# 32u4_pocket.net
KiCad netlist of a schematic drawn in EAGLE
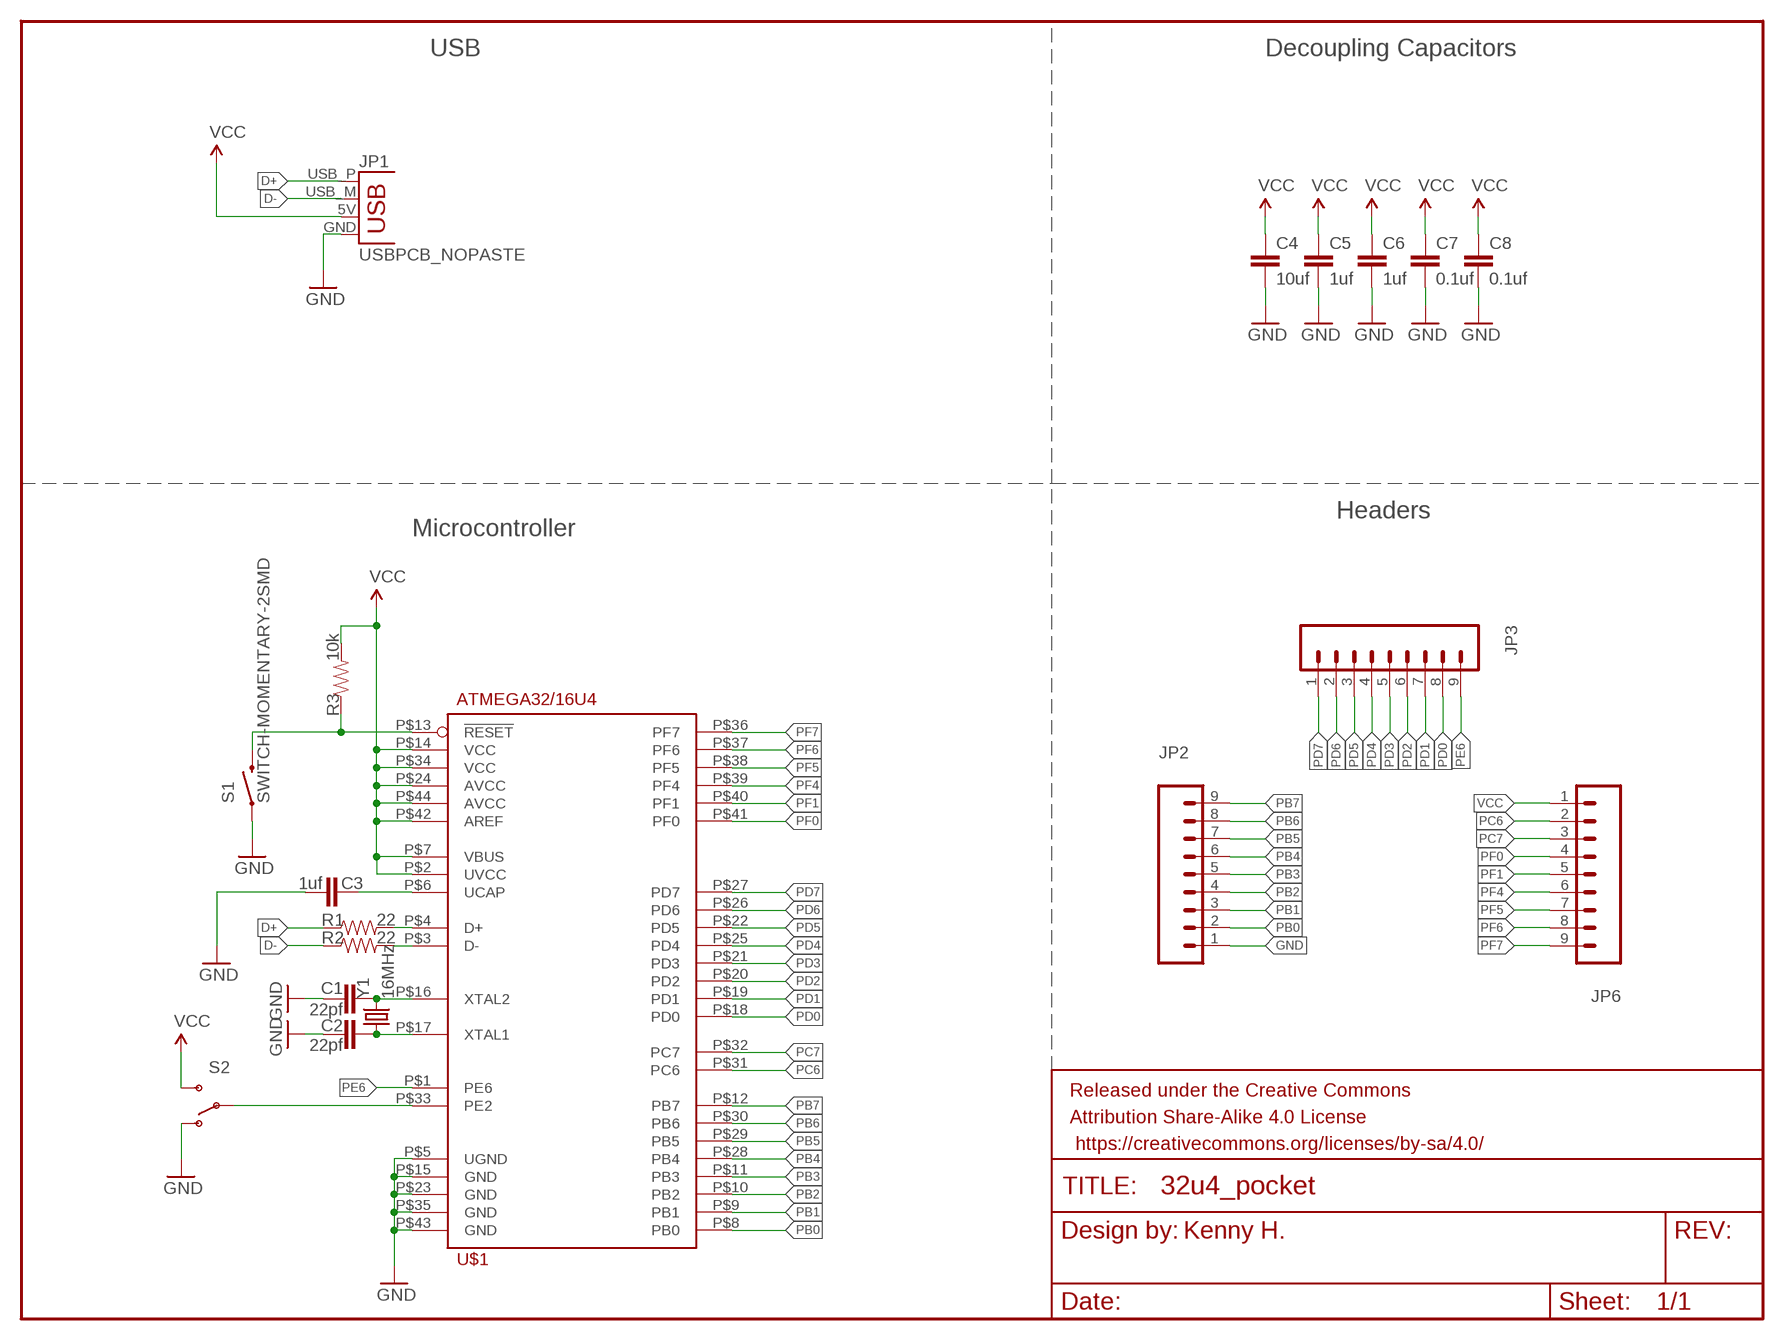
[diagram p0: schematic, sheet 1]

(export (version "E")
  (design (tool "Eeschema 10.0.6"))
  (components
    (comp (ref "C1")
      (value "22pf")
      (footprint "eagle-import:0603-CAP")
      (libsource (lib "eagle-import") (part "CAP0603-CAP"))
    )
    (comp (ref "C2")
      (value "22pf")
      (footprint "eagle-import:0603-CAP")
      (libsource (lib "eagle-import") (part "CAP0603-CAP"))
    )
    (comp (ref "C3")
      (value "1uf")
      (footprint "eagle-import:0603-CAP")
      (libsource (lib "eagle-import") (part "CAP0603-CAP"))
    )
    (comp (ref "C4")
      (value "10uf")
      (footprint "eagle-import:0603-CAP")
      (libsource (lib "eagle-import") (part "CAP0603-CAP"))
    )
    (comp (ref "C5")
      (value "1uf")
      (footprint "eagle-import:0603-CAP")
      (libsource (lib "eagle-import") (part "CAP0603-CAP"))
    )
    (comp (ref "C6")
      (value "1uf")
      (footprint "eagle-import:0603-CAP")
      (libsource (lib "eagle-import") (part "CAP0603-CAP"))
    )
    (comp (ref "C7")
      (value "0.1uf")
      (footprint "eagle-import:0603-CAP")
      (libsource (lib "eagle-import") (part "CAP0603-CAP"))
    )
    (comp (ref "C8")
      (value "0.1uf")
      (footprint "eagle-import:0603-CAP")
      (libsource (lib "eagle-import") (part "CAP0603-CAP"))
    )
    (comp (ref "FRAME1")
      (value "FRAME-LETTER")
      (footprint "eagle-import:CREATIVE_COMMONS")
      (libsource (lib "eagle-import") (part "FRAME-LETTER"))
    )
    (comp (ref "JP1")
      (value "USBPCB_NOPASTE")
      (footprint "eagle-import:USB-A-PCB-NOPASTE")
      (libsource (lib "eagle-import") (part "USBPCB_NOPASTE"))
    )
    (comp (ref "JP2")
      (value "M09LOCK-LONGPADS")
      (footprint "eagle-import:1X09_LOCK_LONGPADS")
      (libsource (lib "eagle-import") (part "M09LOCK-LONGPADS"))
    )
    (comp (ref "JP3")
      (value "M09LOCK-LONGPADS")
      (footprint "eagle-import:1X09_LOCK_LONGPADS")
      (libsource (lib "eagle-import") (part "M09LOCK-LONGPADS"))
    )
    (comp (ref "JP6")
      (value "M09LOCK-LONGPADS")
      (footprint "eagle-import:1X09_LOCK_LONGPADS")
      (libsource (lib "eagle-import") (part "M09LOCK-LONGPADS"))
    )
    (comp (ref "R1")
      (value "22")
      (footprint "eagle-import:0603-RES")
      (libsource (lib "eagle-import") (part "RESISTOR0603-RES"))
    )
    (comp (ref "R2")
      (value "22")
      (footprint "eagle-import:0603-RES")
      (libsource (lib "eagle-import") (part "RESISTOR0603-RES"))
    )
    (comp (ref "R3")
      (value "10k")
      (footprint "eagle-import:0603-RES")
      (libsource (lib "eagle-import") (part "RESISTOR0603-RES"))
    )
    (comp (ref "S1")
      (value "SWITCH-MOMENTARY-2SMD")
      (footprint "eagle-import:TACTILE-SWITCH-SMD")
      (libsource (lib "eagle-import") (part "SWITCH-MOMENTARY-2SMD"))
    )
    (comp (ref "S2")
      (value "SWITCH-SPDT-SMD-A")
      (footprint "eagle-import:SWITCH-SPST-SMD-A")
      (libsource (lib "eagle-import") (part "SWITCH-SPDT-SMD-A"))
    )
    (comp (ref "U$1")
      (value "ATMEGA32/16U4")
      (footprint "eagle-import:TQFP_44_0.8MM")
      (libsource (lib "eagle-import") (part "ATMEGA32/16U4"))
    )
    (comp (ref "Y1")
      (value "16MHz")
      (footprint "eagle-import:HC49US")
      (libsource (lib "eagle-import") (part "CRYSTALHC49US"))
    )
  )
  (nets
    (net (code "1") (name "D+") (class "Default")
      (node (ref "JP1") (pin "USB_P") (pinfunction "D+_USB_P") (pintype "bidirectional"))
      (node (ref "R1") (pin "1") (pinfunction "1_1") (pintype "passive"))
    )
    (net (code "2") (name "D-") (class "Default")
      (node (ref "JP1") (pin "USB_M") (pinfunction "D-_USB_M") (pintype "bidirectional"))
      (node (ref "R2") (pin "1") (pinfunction "1_1") (pintype "passive"))
    )
    (net (code "3") (name "GND") (class "Default")
      (node (ref "C1") (pin "1") (pinfunction "1_1") (pintype "passive"))
      (node (ref "C2") (pin "1") (pinfunction "1_1") (pintype "passive"))
      (node (ref "C3") (pin "2") (pinfunction "2_2") (pintype "passive"))
      (node (ref "C4") (pin "2") (pinfunction "2_2") (pintype "passive"))
      (node (ref "C5") (pin "2") (pinfunction "2_2") (pintype "passive"))
      (node (ref "C6") (pin "2") (pinfunction "2_2") (pintype "passive"))
      (node (ref "C7") (pin "2") (pinfunction "2_2") (pintype "passive"))
      (node (ref "C8") (pin "2") (pinfunction "2_2") (pintype "passive"))
      (node (ref "JP1") (pin "GND") (pinfunction "GND_GND") (pintype "bidirectional"))
      (node (ref "JP2") (pin "1") (pinfunction "1_1") (pintype "passive"))
      (node (ref "S1") (pin "1") (pinfunction "1_1") (pintype "passive"))
      (node (ref "S2") (pin "1") (pinfunction "O_1") (pintype "passive"))
      (node (ref "U$1") (pin "P$15") (pinfunction "GND_P$15") (pintype "power_in"))
      (node (ref "U$1") (pin "P$23") (pinfunction "GND_P$23") (pintype "power_in"))
      (node (ref "U$1") (pin "P$35") (pinfunction "GND_P$35") (pintype "power_in"))
      (node (ref "U$1") (pin "P$43") (pinfunction "GND_P$43") (pintype "power_in"))
      (node (ref "U$1") (pin "P$5") (pinfunction "UGND_P$5") (pintype "power_in"))
    )
    (net (code "4") (name "Net-(S1-2)") (class "Default")
      (node (ref "R3") (pin "1") (pinfunction "1_1") (pintype "passive"))
      (node (ref "S1") (pin "3") (pinfunction "2_3") (pintype "passive"))
      (node (ref "U$1") (pin "P$13") (pinfunction "~{RESET}_P$13") (pintype "input"))
    )
    (net (code "5") (name "Net-(S2-P)") (class "Default")
      (node (ref "S2") (pin "2") (pinfunction "P_2") (pintype "passive"))
      (node (ref "U$1") (pin "P$33") (pinfunction "PE2_P$33") (pintype "bidirectional"))
    )
    (net (code "6") (name "Net-(U$1-D+)") (class "Default")
      (node (ref "R1") (pin "2") (pinfunction "2_2") (pintype "passive"))
      (node (ref "U$1") (pin "P$4") (pinfunction "D+_P$4") (pintype "bidirectional"))
    )
    (net (code "7") (name "Net-(U$1-D-)") (class "Default")
      (node (ref "R2") (pin "2") (pinfunction "2_2") (pintype "passive"))
      (node (ref "U$1") (pin "P$3") (pinfunction "D-_P$3") (pintype "bidirectional"))
    )
    (net (code "8") (name "Net-(U$1-UCAP)") (class "Default")
      (node (ref "C3") (pin "1") (pinfunction "1_1") (pintype "passive"))
      (node (ref "U$1") (pin "P$6") (pinfunction "UCAP_P$6") (pintype "output"))
    )
    (net (code "9") (name "Net-(U$1-XTAL1)") (class "Default")
      (node (ref "C2") (pin "2") (pinfunction "2_2") (pintype "passive"))
      (node (ref "U$1") (pin "P$17") (pinfunction "XTAL1_P$17") (pintype "input"))
      (node (ref "Y1") (pin "1") (pinfunction "1_1") (pintype "passive"))
    )
    (net (code "10") (name "Net-(U$1-XTAL2)") (class "Default")
      (node (ref "C1") (pin "2") (pinfunction "2_2") (pintype "passive"))
      (node (ref "U$1") (pin "P$16") (pinfunction "XTAL2_P$16") (pintype "input"))
      (node (ref "Y1") (pin "2") (pinfunction "2_2") (pintype "passive"))
    )
    (net (code "11") (name "PB0") (class "Default")
      (node (ref "JP2") (pin "2") (pinfunction "2_2") (pintype "passive"))
      (node (ref "U$1") (pin "P$8") (pinfunction "PB0_P$8") (pintype "bidirectional"))
    )
    (net (code "12") (name "PB1") (class "Default")
      (node (ref "JP2") (pin "3") (pinfunction "3_3") (pintype "passive"))
      (node (ref "U$1") (pin "P$9") (pinfunction "PB1_P$9") (pintype "bidirectional"))
    )
    (net (code "13") (name "PB2") (class "Default")
      (node (ref "JP2") (pin "4") (pinfunction "4_4") (pintype "passive"))
      (node (ref "U$1") (pin "P$10") (pinfunction "PB2_P$10") (pintype "bidirectional"))
    )
    (net (code "14") (name "PB3") (class "Default")
      (node (ref "JP2") (pin "5") (pinfunction "5_5") (pintype "passive"))
      (node (ref "U$1") (pin "P$11") (pinfunction "PB3_P$11") (pintype "bidirectional"))
    )
    (net (code "15") (name "PB4") (class "Default")
      (node (ref "JP2") (pin "6") (pinfunction "6_6") (pintype "passive"))
      (node (ref "U$1") (pin "P$28") (pinfunction "PB4_P$28") (pintype "bidirectional"))
    )
    (net (code "16") (name "PB5") (class "Default")
      (node (ref "JP2") (pin "7") (pinfunction "7_7") (pintype "passive"))
      (node (ref "U$1") (pin "P$29") (pinfunction "PB5_P$29") (pintype "bidirectional"))
    )
    (net (code "17") (name "PB6") (class "Default")
      (node (ref "JP2") (pin "8") (pinfunction "8_8") (pintype "passive"))
      (node (ref "U$1") (pin "P$30") (pinfunction "PB6_P$30") (pintype "bidirectional"))
    )
    (net (code "18") (name "PB7") (class "Default")
      (node (ref "JP2") (pin "9") (pinfunction "9_9") (pintype "passive"))
      (node (ref "U$1") (pin "P$12") (pinfunction "PB7_P$12") (pintype "bidirectional"))
    )
    (net (code "19") (name "PC6") (class "Default")
      (node (ref "JP6") (pin "2") (pinfunction "2_2") (pintype "passive"))
      (node (ref "U$1") (pin "P$31") (pinfunction "PC6_P$31") (pintype "bidirectional"))
    )
    (net (code "20") (name "PC7") (class "Default")
      (node (ref "JP6") (pin "3") (pinfunction "3_3") (pintype "passive"))
      (node (ref "U$1") (pin "P$32") (pinfunction "PC7_P$32") (pintype "bidirectional"))
    )
    (net (code "21") (name "PD0") (class "Default")
      (node (ref "JP3") (pin "8") (pinfunction "8_8") (pintype "passive"))
      (node (ref "U$1") (pin "P$18") (pinfunction "PD0_P$18") (pintype "bidirectional"))
    )
    (net (code "22") (name "PD1") (class "Default")
      (node (ref "JP3") (pin "7") (pinfunction "7_7") (pintype "passive"))
      (node (ref "U$1") (pin "P$19") (pinfunction "PD1_P$19") (pintype "bidirectional"))
    )
    (net (code "23") (name "PD2") (class "Default")
      (node (ref "JP3") (pin "6") (pinfunction "6_6") (pintype "passive"))
      (node (ref "U$1") (pin "P$20") (pinfunction "PD2_P$20") (pintype "bidirectional"))
    )
    (net (code "24") (name "PD3") (class "Default")
      (node (ref "JP3") (pin "5") (pinfunction "5_5") (pintype "passive"))
      (node (ref "U$1") (pin "P$21") (pinfunction "PD3_P$21") (pintype "bidirectional"))
    )
    (net (code "25") (name "PD4") (class "Default")
      (node (ref "JP3") (pin "4") (pinfunction "4_4") (pintype "passive"))
      (node (ref "U$1") (pin "P$25") (pinfunction "PD4_P$25") (pintype "bidirectional"))
    )
    (net (code "26") (name "PD5") (class "Default")
      (node (ref "JP3") (pin "3") (pinfunction "3_3") (pintype "passive"))
      (node (ref "U$1") (pin "P$22") (pinfunction "PD5_P$22") (pintype "bidirectional"))
    )
    (net (code "27") (name "PD6") (class "Default")
      (node (ref "JP3") (pin "2") (pinfunction "2_2") (pintype "passive"))
      (node (ref "U$1") (pin "P$26") (pinfunction "PD6_P$26") (pintype "bidirectional"))
    )
    (net (code "28") (name "PD7") (class "Default")
      (node (ref "JP3") (pin "1") (pinfunction "1_1") (pintype "passive"))
      (node (ref "U$1") (pin "P$27") (pinfunction "PD7_P$27") (pintype "bidirectional"))
    )
    (net (code "29") (name "PE6") (class "Default")
      (node (ref "JP3") (pin "9") (pinfunction "9_9") (pintype "passive"))
      (node (ref "U$1") (pin "P$1") (pinfunction "PE6_P$1") (pintype "bidirectional"))
    )
    (net (code "30") (name "PF0") (class "Default")
      (node (ref "JP6") (pin "4") (pinfunction "4_4") (pintype "passive"))
      (node (ref "U$1") (pin "P$41") (pinfunction "PF0_P$41") (pintype "bidirectional"))
    )
    (net (code "31") (name "PF1") (class "Default")
      (node (ref "JP6") (pin "5") (pinfunction "5_5") (pintype "passive"))
      (node (ref "U$1") (pin "P$40") (pinfunction "PF1_P$40") (pintype "bidirectional"))
    )
    (net (code "32") (name "PF4") (class "Default")
      (node (ref "JP6") (pin "6") (pinfunction "6_6") (pintype "passive"))
      (node (ref "U$1") (pin "P$39") (pinfunction "PF4_P$39") (pintype "bidirectional"))
    )
    (net (code "33") (name "PF5") (class "Default")
      (node (ref "JP6") (pin "7") (pinfunction "7_7") (pintype "passive"))
      (node (ref "U$1") (pin "P$38") (pinfunction "PF5_P$38") (pintype "bidirectional"))
    )
    (net (code "34") (name "PF6") (class "Default")
      (node (ref "JP6") (pin "8") (pinfunction "8_8") (pintype "passive"))
      (node (ref "U$1") (pin "P$37") (pinfunction "PF6_P$37") (pintype "bidirectional"))
    )
    (net (code "35") (name "PF7") (class "Default")
      (node (ref "JP6") (pin "9") (pinfunction "9_9") (pintype "passive"))
      (node (ref "U$1") (pin "P$36") (pinfunction "PF7_P$36") (pintype "bidirectional"))
    )
    (net (code "36") (name "VCC") (class "Default")
      (node (ref "C4") (pin "1") (pinfunction "1_1") (pintype "passive"))
      (node (ref "C5") (pin "1") (pinfunction "1_1") (pintype "passive"))
      (node (ref "C6") (pin "1") (pinfunction "1_1") (pintype "passive"))
      (node (ref "C7") (pin "1") (pinfunction "1_1") (pintype "passive"))
      (node (ref "C8") (pin "1") (pinfunction "1_1") (pintype "passive"))
      (node (ref "JP1") (pin "5V") (pinfunction "VBUS_5V") (pintype "bidirectional"))
      (node (ref "JP6") (pin "1") (pinfunction "1_1") (pintype "passive"))
      (node (ref "R3") (pin "2") (pinfunction "2_2") (pintype "passive"))
      (node (ref "S2") (pin "3") (pinfunction "S_3") (pintype "passive"))
      (node (ref "U$1") (pin "P$14") (pinfunction "VCC_P$14") (pintype "power_in"))
      (node (ref "U$1") (pin "P$2") (pinfunction "UVCC_P$2") (pintype "power_in"))
      (node (ref "U$1") (pin "P$24") (pinfunction "AVCC_P$24") (pintype "power_in"))
      (node (ref "U$1") (pin "P$34") (pinfunction "VCC_P$34") (pintype "power_in"))
      (node (ref "U$1") (pin "P$42") (pinfunction "AREF_P$42") (pintype "power_in"))
      (node (ref "U$1") (pin "P$44") (pinfunction "AVCC_P$44") (pintype "power_in"))
      (node (ref "U$1") (pin "P$7") (pinfunction "VBUS_P$7") (pintype "power_in"))
    )
  )
)
